# 140703_AriloTX_REV2_1_0.net
KiCad netlist of a schematic drawn in EAGLE
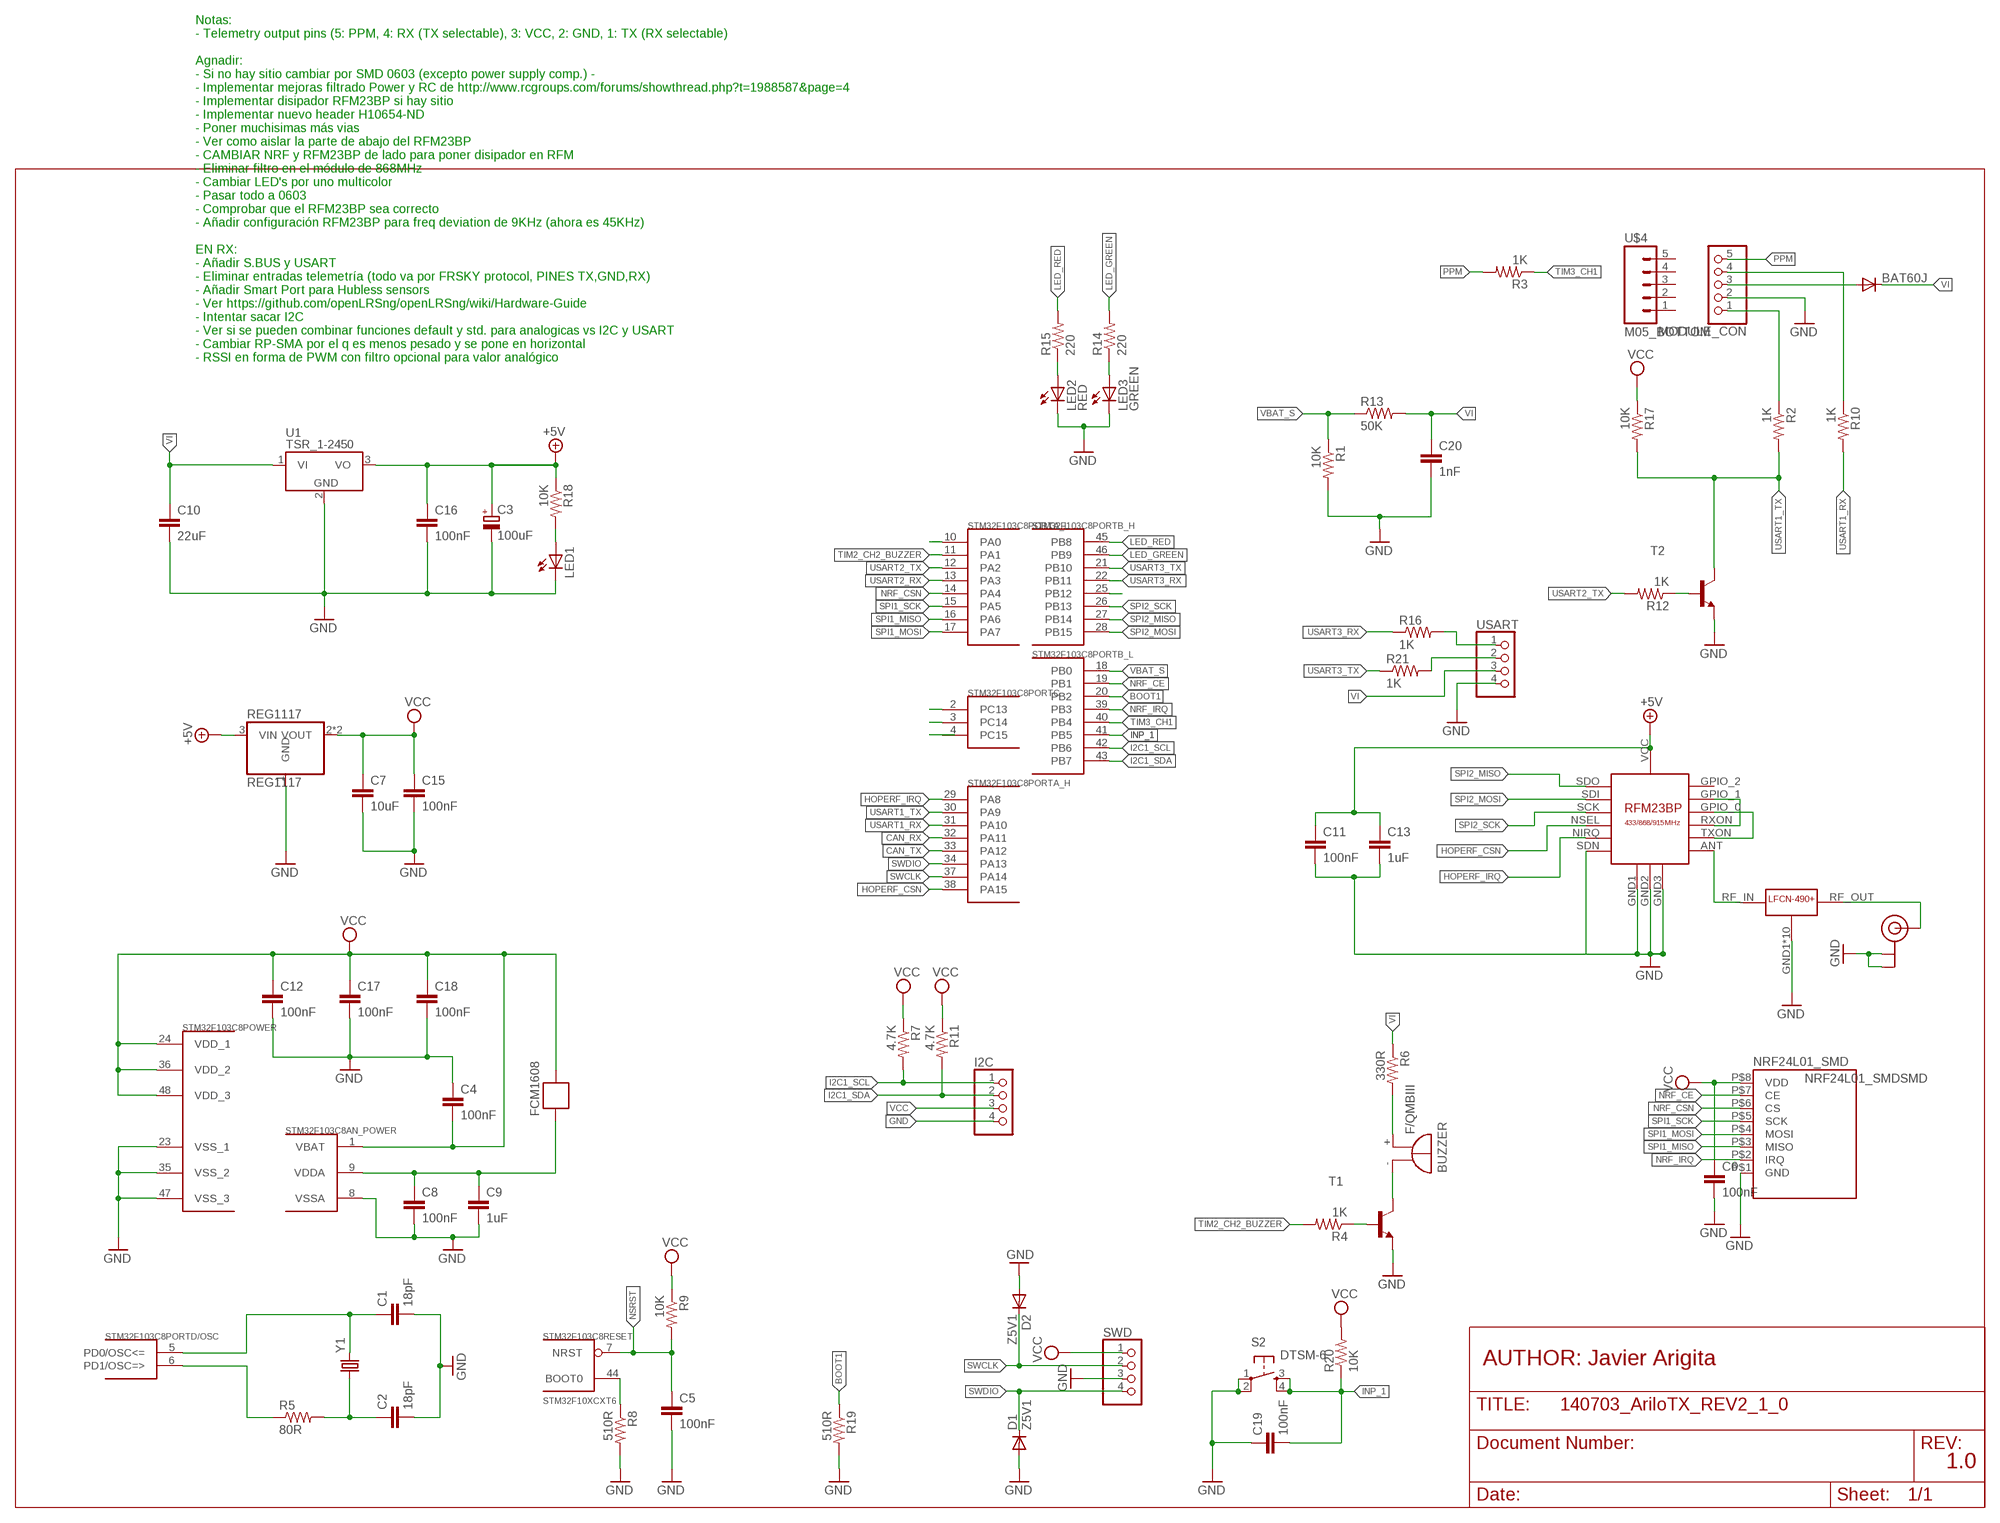
[diagram p0: schematic, sheet 1]

(export (version "E")
  (design (tool "Eeschema 10.0.6"))
  (components
    (comp (ref "BAT60J")
      (value "DIODE-SOD323-R")
      (footprint "eagle-import:SOD323-R")
      (libsource (lib "eagle-import") (part "DIODE-SOD323-R"))
    )
    (comp (ref "BUZZER")
      (value "F/QMBIII")
      (footprint "eagle-import:F_QMBIII")
      (libsource (lib "eagle-import") (part "F/QMBIII"))
    )
    (comp (ref "C1")
      (value "18pF")
      (footprint "eagle-import:C0805")
      (libsource (lib "eagle-import") (part "C-EUC0805"))
    )
    (comp (ref "C2")
      (value "18pF")
      (footprint "eagle-import:C0805")
      (libsource (lib "eagle-import") (part "C-EUC0805"))
    )
    (comp (ref "C3")
      (value "100uF")
      (footprint "eagle-import:SMC_B")
      (libsource (lib "eagle-import") (part "CPOL-EUSMCB"))
    )
    (comp (ref "C4")
      (value "100nF")
      (footprint "eagle-import:C0805")
      (libsource (lib "eagle-import") (part "C-EUC0805"))
    )
    (comp (ref "C5")
      (value "100nF")
      (footprint "eagle-import:C0805")
      (libsource (lib "eagle-import") (part "C-EUC0805"))
    )
    (comp (ref "C6")
      (value "100nF")
      (footprint "eagle-import:C0805")
      (libsource (lib "eagle-import") (part "C-EUC0805"))
    )
    (comp (ref "C7")
      (value "10uF")
      (footprint "eagle-import:C0805")
      (libsource (lib "eagle-import") (part "C-EUC0805"))
    )
    (comp (ref "C8")
      (value "100nF")
      (footprint "eagle-import:C0805")
      (libsource (lib "eagle-import") (part "C-EUC0805"))
    )
    (comp (ref "C9")
      (value "1uF")
      (footprint "eagle-import:C3216")
      (libsource (lib "eagle-import") (part "resistor_C-EUC3216"))
    )
    (comp (ref "C10")
      (value "22uF")
      (footprint "eagle-import:C3216")
      (libsource (lib "eagle-import") (part "resistor_C-EUC3216"))
    )
    (comp (ref "C11")
      (value "100nF")
      (footprint "eagle-import:C0805")
      (libsource (lib "eagle-import") (part "C-EUC0805"))
    )
    (comp (ref "C12")
      (value "100nF")
      (footprint "eagle-import:C0805")
      (libsource (lib "eagle-import") (part "C-EUC0805"))
    )
    (comp (ref "C13")
      (value "1uF")
      (footprint "eagle-import:C3216")
      (libsource (lib "eagle-import") (part "resistor_C-EUC3216"))
    )
    (comp (ref "C15")
      (value "100nF")
      (footprint "eagle-import:C0805")
      (libsource (lib "eagle-import") (part "C-EUC0805"))
    )
    (comp (ref "C16")
      (value "100nF")
      (footprint "eagle-import:C0805")
      (libsource (lib "eagle-import") (part "C-EUC0805"))
    )
    (comp (ref "C17")
      (value "100nF")
      (footprint "eagle-import:C0805")
      (libsource (lib "eagle-import") (part "C-EUC0805"))
    )
    (comp (ref "C18")
      (value "100nF")
      (footprint "eagle-import:C0805")
      (libsource (lib "eagle-import") (part "C-EUC0805"))
    )
    (comp (ref "C19")
      (value "100nF")
      (footprint "eagle-import:C0805")
      (libsource (lib "eagle-import") (part "C-EUC0805"))
    )
    (comp (ref "C20")
      (value "1nF")
      (footprint "eagle-import:C0805")
      (libsource (lib "eagle-import") (part "C-EUC0805"))
    )
    (comp (ref "D1")
      (value "Z5V1")
      (footprint "eagle-import:SOD323-R")
      (libsource (lib "eagle-import") (part "DIODE-SOD323-R"))
    )
    (comp (ref "D2")
      (value "Z5V1")
      (footprint "eagle-import:SOD323-R")
      (libsource (lib "eagle-import") (part "DIODE-SOD323-R"))
    )
    (comp (ref "FCM1608")
      (value "FERRITE-BEAD")
      (footprint "eagle-import:R0603")
      (libsource (lib "eagle-import") (part "FERRITE-BEAD"))
    )
    (comp (ref "I2C")
      (value "PINHD-1X4")
      (footprint "eagle-import:1X04")
      (libsource (lib "eagle-import") (part "PINHD-1X4"))
    )
    (comp (ref "LED1")
      (value "LED0805")
      (footprint "eagle-import:CHIPLED_0805")
      (libsource (lib "eagle-import") (part "LED0805"))
    )
    (comp (ref "LED2")
      (value "RED")
      (footprint "eagle-import:CHIP-LED0805")
      (libsource (lib "eagle-import") (part "LEDCHIP-LED0805"))
    )
    (comp (ref "LED3")
      (value "GREEN")
      (footprint "eagle-import:CHIP-LED0805")
      (libsource (lib "eagle-import") (part "LEDCHIP-LED0805"))
    )
    (comp (ref "MODULE_CON")
      (value "PINHD-1X5")
      (footprint "eagle-import:1X05")
      (libsource (lib "eagle-import") (part "PINHD-1X5"))
    )
    (comp (ref "NRF24L01_SMD")
      (value "NRF24L01_SMDSMD")
      (footprint "eagle-import:NRF24L01_SMD")
      (libsource (lib "eagle-import") (part "NRF24L01_SMDSMD"))
    )
    (comp (ref "R1")
      (value "10K")
      (footprint "eagle-import:R0805")
      (libsource (lib "eagle-import") (part "RESISTOR0805"))
    )
    (comp (ref "R2")
      (value "1K")
      (footprint "eagle-import:R0805")
      (libsource (lib "eagle-import") (part "RESISTOR0805"))
    )
    (comp (ref "R3")
      (value "1K")
      (footprint "eagle-import:R0805")
      (libsource (lib "eagle-import") (part "RESISTOR0805"))
    )
    (comp (ref "R4")
      (value "1K")
      (footprint "eagle-import:R0805")
      (libsource (lib "eagle-import") (part "RESISTOR0805"))
    )
    (comp (ref "R5")
      (value "80R")
      (footprint "eagle-import:R0805")
      (libsource (lib "eagle-import") (part "RESISTOR0805"))
    )
    (comp (ref "R6")
      (value "330R")
      (footprint "eagle-import:R0805")
      (libsource (lib "eagle-import") (part "RESISTOR0805"))
    )
    (comp (ref "R7")
      (value "4.7K")
      (footprint "eagle-import:R0805")
      (libsource (lib "eagle-import") (part "RESISTOR0805"))
    )
    (comp (ref "R8")
      (value "510R")
      (footprint "eagle-import:R0805")
      (libsource (lib "eagle-import") (part "RESISTOR0805"))
    )
    (comp (ref "R9")
      (value "10K")
      (footprint "eagle-import:R0805")
      (libsource (lib "eagle-import") (part "RESISTOR0805"))
    )
    (comp (ref "R10")
      (value "1K")
      (footprint "eagle-import:R0805")
      (libsource (lib "eagle-import") (part "RESISTOR0805"))
    )
    (comp (ref "R11")
      (value "4.7K")
      (footprint "eagle-import:R0805")
      (libsource (lib "eagle-import") (part "RESISTOR0805"))
    )
    (comp (ref "R12")
      (value "1K")
      (footprint "eagle-import:R0805")
      (libsource (lib "eagle-import") (part "RESISTOR0805"))
    )
    (comp (ref "R13")
      (value "50K")
      (footprint "eagle-import:R0805")
      (libsource (lib "eagle-import") (part "RESISTOR0805"))
    )
    (comp (ref "R14")
      (value "220")
      (footprint "eagle-import:R0805")
      (libsource (lib "eagle-import") (part "RESISTOR0805"))
    )
    (comp (ref "R15")
      (value "220")
      (footprint "eagle-import:R0805")
      (libsource (lib "eagle-import") (part "RESISTOR0805"))
    )
    (comp (ref "R16")
      (value "1K")
      (footprint "eagle-import:R0805")
      (libsource (lib "eagle-import") (part "RESISTOR0805"))
    )
    (comp (ref "R17")
      (value "10K")
      (footprint "eagle-import:R0805")
      (libsource (lib "eagle-import") (part "RESISTOR0805"))
    )
    (comp (ref "R18")
      (value "10K")
      (footprint "eagle-import:R0805")
      (libsource (lib "eagle-import") (part "RESISTOR0805"))
    )
    (comp (ref "R19")
      (value "510R")
      (footprint "eagle-import:R0805")
      (libsource (lib "eagle-import") (part "RESISTOR0805"))
    )
    (comp (ref "R20")
      (value "10K")
      (footprint "eagle-import:R0805")
      (libsource (lib "eagle-import") (part "RESISTOR0805"))
    )
    (comp (ref "R21")
      (value "1K")
      (footprint "eagle-import:R0805")
      (libsource (lib "eagle-import") (part "RESISTOR0805"))
    )
    (comp (ref "REG1117")
      (value "REG1117")
      (footprint "eagle-import:SOT223")
      (libsource (lib "eagle-import") (part "REG1117"))
    )
    (comp (ref "S2")
      (value "DTSM-6")
      (footprint "eagle-import:DTSM-6")
      (libsource (lib "eagle-import") (part "DTSM-6"))
    )
    (comp (ref "STM32F103C8")
      (value "STM32F10XCXT6")
      (footprint "eagle-import:TQFP48")
      (libsource (lib "eagle-import") (part "STM32F10XCXT6"))
    )
    (comp (ref "SWD")
      (value "PINHD-1X4")
      (footprint "eagle-import:1X04")
      (libsource (lib "eagle-import") (part "PINHD-1X4"))
    )
    (comp (ref "T1")
      (value "BC848-NPN-SOT23-BEC")
      (footprint "eagle-import:SOT23-BEC")
      (libsource (lib "eagle-import") (part "-NPN-SOT23-BECBC848"))
    )
    (comp (ref "T2")
      (value "BC848-NPN-SOT23-BEC")
      (footprint "eagle-import:SOT23-BEC")
      (libsource (lib "eagle-import") (part "-NPN-SOT23-BECBC848"))
    )
    (comp (ref "U$1")
      (value "RFM23BP")
      (footprint "eagle-import:RFM23BP")
      (libsource (lib "eagle-import") (part "RFM23BP"))
    )
    (comp (ref "U$2")
      (value "LFCN490+")
      (footprint "eagle-import:LFCN490+")
      (libsource (lib "eagle-import") (part "LFCN490+"))
    )
    (comp (ref "U$3")
      (value "U.FL")
      (footprint "eagle-import:U.FL")
      (libsource (lib "eagle-import") (part "U.FL"))
    )
    (comp (ref "U$4")
      (value "M05_BOTTOM")
      (footprint "eagle-import:M05_BOTTOM")
      (libsource (lib "eagle-import") (part "M05_BOTTOM"))
    )
    (comp (ref "U1")
      (value "TSR_1-2450")
      (footprint "eagle-import:TSR-1")
      (libsource (lib "eagle-import") (part "TSR_1-2450"))
    )
    (comp (ref "USART")
      (value "PINHD-1X4")
      (footprint "eagle-import:1X04")
      (libsource (lib "eagle-import") (part "PINHD-1X4"))
    )
    (comp (ref "Y1")
      (value "CRYSTAL5X3")
      (footprint "eagle-import:CRYSTAL-SMD-5X3")
      (libsource (lib "eagle-import") (part "CRYSTAL5X3"))
    )
  )
  (nets
    (net (code "1") (name "+5V") (class "Default")
      (node (ref "C11") (pin "1") (pinfunction "1_1") (pintype "passive"))
      (node (ref "C13") (pin "1") (pinfunction "1_1") (pintype "passive"))
      (node (ref "C16") (pin "1") (pinfunction "1_1") (pintype "passive"))
      (node (ref "C3") (pin "+") (pinfunction "+_+") (pintype "passive"))
      (node (ref "R18") (pin "1") (pinfunction "1_1") (pintype "passive"))
      (node (ref "REG1117") (pin "3") (pinfunction "VIN_3") (pintype "input"))
      (node (ref "U$1") (pin "VCC") (pinfunction "VCC_VCC") (pintype "power_in"))
      (node (ref "U1") (pin "3") (pinfunction "VO_3") (pintype "power_in"))
    )
    (net (code "2") (name "BOOT1") (class "Default")
      (node (ref "R19") (pin "1") (pinfunction "1_1") (pintype "passive"))
      (node (ref "STM32F103C8") (pin "20") (pinfunction "PB2_20") (pintype "bidirectional"))
    )
    (net (code "3") (name "CAN_RX") (class "Default")
      (node (ref "STM32F103C8") (pin "32") (pinfunction "PA11_32") (pintype "bidirectional"))
    )
    (net (code "4") (name "CAN_TX") (class "Default")
      (node (ref "STM32F103C8") (pin "33") (pinfunction "PA12_33") (pintype "bidirectional"))
    )
    (net (code "5") (name "GND") (class "Default")
      (node (ref "C1") (pin "2") (pinfunction "2_2") (pintype "passive"))
      (node (ref "C10") (pin "2") (pinfunction "2_2") (pintype "passive"))
      (node (ref "C11") (pin "2") (pinfunction "2_2") (pintype "passive"))
      (node (ref "C12") (pin "2") (pinfunction "2_2") (pintype "passive"))
      (node (ref "C13") (pin "2") (pinfunction "2_2") (pintype "passive"))
      (node (ref "C15") (pin "2") (pinfunction "2_2") (pintype "passive"))
      (node (ref "C16") (pin "2") (pinfunction "2_2") (pintype "passive"))
      (node (ref "C17") (pin "2") (pinfunction "2_2") (pintype "passive"))
      (node (ref "C18") (pin "2") (pinfunction "2_2") (pintype "passive"))
      (node (ref "C19") (pin "1") (pinfunction "1_1") (pintype "passive"))
      (node (ref "C2") (pin "2") (pinfunction "2_2") (pintype "passive"))
      (node (ref "C20") (pin "2") (pinfunction "2_2") (pintype "passive"))
      (node (ref "C3") (pin "-") (pinfunction "-_-") (pintype "passive"))
      (node (ref "C4") (pin "1") (pinfunction "1_1") (pintype "passive"))
      (node (ref "C5") (pin "2") (pinfunction "2_2") (pintype "passive"))
      (node (ref "C6") (pin "2") (pinfunction "2_2") (pintype "passive"))
      (node (ref "C7") (pin "2") (pinfunction "2_2") (pintype "passive"))
      (node (ref "C8") (pin "2") (pinfunction "2_2") (pintype "passive"))
      (node (ref "C9") (pin "2") (pinfunction "2_2") (pintype "passive"))
      (node (ref "D1") (pin "A") (pinfunction "A_A") (pintype "passive"))
      (node (ref "D2") (pin "A") (pinfunction "A_A") (pintype "passive"))
      (node (ref "I2C") (pin "4") (pinfunction "4_4") (pintype "passive"))
      (node (ref "LED1") (pin "C") (pinfunction "C_C") (pintype "passive"))
      (node (ref "LED2") (pin "C") (pinfunction "C_C") (pintype "passive"))
      (node (ref "LED3") (pin "C") (pinfunction "C_C") (pintype "passive"))
      (node (ref "MODULE_CON") (pin "2") (pinfunction "2_2") (pintype "passive"))
      (node (ref "NRF24L01_SMD") (pin "P$1") (pinfunction "GND_P$1") (pintype "power_in"))
      (node (ref "R1") (pin "2") (pinfunction "2_2") (pintype "passive"))
      (node (ref "R19") (pin "2") (pinfunction "2_2") (pintype "passive"))
      (node (ref "R8") (pin "2") (pinfunction "2_2") (pintype "passive"))
      (node (ref "REG1117") (pin "1") (pinfunction "GND_1") (pintype "power_in"))
      (node (ref "S2") (pin "1") (pinfunction "1_1") (pintype "passive"))
      (node (ref "S2") (pin "2") (pinfunction "2_2") (pintype "passive"))
      (node (ref "STM32F103C8") (pin "23") (pinfunction "VSS_1_23") (pintype "power_in"))
      (node (ref "STM32F103C8") (pin "35") (pinfunction "VSS_2_35") (pintype "power_in"))
      (node (ref "STM32F103C8") (pin "47") (pinfunction "VSS_3_47") (pintype "power_in"))
      (node (ref "STM32F103C8") (pin "8") (pinfunction "VSSA_8") (pintype "power_in"))
      (node (ref "SWD") (pin "3") (pinfunction "3_3") (pintype "passive"))
      (node (ref "T1") (pin "E") (pinfunction "E_E") (pintype "passive"))
      (node (ref "T2") (pin "E") (pinfunction "E_E") (pintype "passive"))
      (node (ref "U$1") (pin "GND1") (pinfunction "GND1_GND1") (pintype "power_in"))
      (node (ref "U$1") (pin "GND2") (pinfunction "GND2_GND2") (pintype "power_in"))
      (node (ref "U$1") (pin "GND3") (pinfunction "GND3_GND3") (pintype "power_in"))
      (node (ref "U$1") (pin "SDN") (pinfunction "SDN_SDN") (pintype "bidirectional"))
      (node (ref "U$2") (pin "GND1") (pinfunction "GND_GND1") (pintype "bidirectional"))
      (node (ref "U$2") (pin "GND10") (pinfunction "GND_GND10") (pintype "bidirectional"))
      (node (ref "U$2") (pin "GND2") (pinfunction "GND_GND2") (pintype "bidirectional"))
      (node (ref "U$2") (pin "GND3") (pinfunction "GND_GND3") (pintype "bidirectional"))
      (node (ref "U$2") (pin "GND4") (pinfunction "GND_GND4") (pintype "bidirectional"))
      (node (ref "U$2") (pin "GND5") (pinfunction "GND_GND5") (pintype "bidirectional"))
      (node (ref "U$2") (pin "GND6") (pinfunction "GND_GND6") (pintype "bidirectional"))
      (node (ref "U$2") (pin "GND7") (pinfunction "GND_GND7") (pintype "bidirectional"))
      (node (ref "U$2") (pin "GND8") (pinfunction "GND_GND8") (pintype "bidirectional"))
      (node (ref "U$2") (pin "GND9") (pinfunction "GND_GND9") (pintype "bidirectional"))
      (node (ref "U$3") (pin "P$1") (pinfunction "GND_P$1") (pintype "bidirectional"))
      (node (ref "U$3") (pin "P$2") (pinfunction "GND_P$2") (pintype "bidirectional"))
      (node (ref "U1") (pin "2") (pinfunction "GND_2") (pintype "power_in"))
      (node (ref "USART") (pin "4") (pinfunction "4_4") (pintype "passive"))
    )
    (net (code "6") (name "HOPERF_CSN") (class "Default")
      (node (ref "STM32F103C8") (pin "38") (pinfunction "PA15_38") (pintype "bidirectional"))
      (node (ref "U$1") (pin "NSEL") (pinfunction "NSEL_NSEL") (pintype "bidirectional"))
    )
    (net (code "7") (name "HOPERF_IRQ") (class "Default")
      (node (ref "STM32F103C8") (pin "29") (pinfunction "PA8_29") (pintype "bidirectional"))
      (node (ref "U$1") (pin "NIRQ") (pinfunction "NIRQ_NIRQ") (pintype "bidirectional"))
    )
    (net (code "8") (name "I2C1_SCL") (class "Default")
      (node (ref "I2C") (pin "1") (pinfunction "1_1") (pintype "passive"))
      (node (ref "R7") (pin "2") (pinfunction "2_2") (pintype "passive"))
      (node (ref "STM32F103C8") (pin "42") (pinfunction "PB6_42") (pintype "bidirectional"))
    )
    (net (code "9") (name "I2C1_SDA") (class "Default")
      (node (ref "I2C") (pin "2") (pinfunction "2_2") (pintype "passive"))
      (node (ref "R11") (pin "2") (pinfunction "2_2") (pintype "passive"))
      (node (ref "STM32F103C8") (pin "43") (pinfunction "PB7_43") (pintype "bidirectional"))
    )
    (net (code "10") (name "INP_1") (class "Default")
      (node (ref "C19") (pin "2") (pinfunction "2_2") (pintype "passive"))
      (node (ref "R20") (pin "1") (pinfunction "1_1") (pintype "passive"))
      (node (ref "S2") (pin "3") (pinfunction "3_3") (pintype "passive"))
      (node (ref "S2") (pin "4") (pinfunction "4_4") (pintype "passive"))
      (node (ref "STM32F103C8") (pin "41") (pinfunction "PB5_41") (pintype "bidirectional"))
    )
    (net (code "11") (name "LED_GREEN") (class "Default")
      (node (ref "R14") (pin "2") (pinfunction "2_2") (pintype "passive"))
      (node (ref "STM32F103C8") (pin "46") (pinfunction "PB9_46") (pintype "bidirectional"))
    )
    (net (code "12") (name "LED_RED") (class "Default")
      (node (ref "R15") (pin "2") (pinfunction "2_2") (pintype "passive"))
      (node (ref "STM32F103C8") (pin "45") (pinfunction "PB8_45") (pintype "bidirectional"))
    )
    (net (code "13") (name "NRF_CE") (class "Default")
      (node (ref "NRF24L01_SMD") (pin "P$7") (pinfunction "CE_P$7") (pintype "input"))
      (node (ref "STM32F103C8") (pin "19") (pinfunction "PB1_19") (pintype "bidirectional"))
    )
    (net (code "14") (name "NRF_CSN") (class "Default")
      (node (ref "NRF24L01_SMD") (pin "P$6") (pinfunction "CS_P$6") (pintype "input"))
      (node (ref "STM32F103C8") (pin "14") (pinfunction "PA4_14") (pintype "bidirectional"))
    )
    (net (code "15") (name "NRF_IRQ") (class "Default")
      (node (ref "NRF24L01_SMD") (pin "P$2") (pinfunction "IRQ_P$2") (pintype "output"))
      (node (ref "STM32F103C8") (pin "39") (pinfunction "PB3_39") (pintype "bidirectional"))
    )
    (net (code "16") (name "NSRST") (class "Default")
      (node (ref "C5") (pin "1") (pinfunction "1_1") (pintype "passive"))
      (node (ref "R9") (pin "2") (pinfunction "2_2") (pintype "passive"))
      (node (ref "STM32F103C8") (pin "7") (pinfunction "NRST_7") (pintype "input"))
    )
    (net (code "17") (name "Net-(BAT60J-PadA)") (class "Default")
      (node (ref "BAT60J") (pin "A") (pinfunction "A_A") (pintype "passive"))
      (node (ref "MODULE_CON") (pin "3") (pinfunction "3_3") (pintype "passive"))
    )
    (net (code "18") (name "Net-(BUZZER-+)") (class "Default")
      (node (ref "BUZZER") (pin "-") (pinfunction "+_-") (pintype "passive"))
      (node (ref "T1") (pin "C") (pinfunction "C_C") (pintype "passive"))
    )
    (net (code "19") (name "Net-(BUZZER--)") (class "Default")
      (node (ref "BUZZER") (pin "+") (pinfunction "-_+") (pintype "passive"))
      (node (ref "R6") (pin "2") (pinfunction "2_2") (pintype "passive"))
    )
    (net (code "20") (name "Net-(C2-Pad1)") (class "Default")
      (node (ref "C2") (pin "1") (pinfunction "1_1") (pintype "passive"))
      (node (ref "R5") (pin "2") (pinfunction "2_2") (pintype "passive"))
      (node (ref "Y1") (pin "1") (pinfunction "1_1") (pintype "passive"))
    )
    (net (code "21") (name "Net-(FCM1608-P$2)") (class "Default")
      (node (ref "C8") (pin "1") (pinfunction "1_1") (pintype "passive"))
      (node (ref "C9") (pin "1") (pinfunction "1_1") (pintype "passive"))
      (node (ref "FCM1608") (pin "2") (pinfunction "P$2_2") (pintype "bidirectional"))
      (node (ref "STM32F103C8") (pin "9") (pinfunction "VDDA_9") (pintype "power_in"))
    )
    (net (code "22") (name "Net-(LED1-PadA)") (class "Default")
      (node (ref "LED1") (pin "A") (pinfunction "A_A") (pintype "passive"))
      (node (ref "R18") (pin "2") (pinfunction "2_2") (pintype "passive"))
    )
    (net (code "23") (name "Net-(LED2-PadA)") (class "Default")
      (node (ref "LED2") (pin "A") (pinfunction "A_A") (pintype "passive"))
      (node (ref "R15") (pin "1") (pinfunction "1_1") (pintype "passive"))
    )
    (net (code "24") (name "Net-(LED3-PadA)") (class "Default")
      (node (ref "LED3") (pin "A") (pinfunction "A_A") (pintype "passive"))
      (node (ref "R14") (pin "1") (pinfunction "1_1") (pintype "passive"))
    )
    (net (code "25") (name "Net-(MODULE_CON-Pad1)") (class "Default")
      (node (ref "MODULE_CON") (pin "1") (pinfunction "1_1") (pintype "passive"))
      (node (ref "R2") (pin "1") (pinfunction "1_1") (pintype "passive"))
    )
    (net (code "26") (name "Net-(MODULE_CON-Pad4)") (class "Default")
      (node (ref "MODULE_CON") (pin "4") (pinfunction "4_4") (pintype "passive"))
      (node (ref "R10") (pin "1") (pinfunction "1_1") (pintype "passive"))
    )
    (net (code "27") (name "Net-(R4-Pad1)") (class "Default")
      (node (ref "R4") (pin "1") (pinfunction "1_1") (pintype "passive"))
      (node (ref "T1") (pin "B") (pinfunction "B_B") (pintype "passive"))
    )
    (net (code "28") (name "Net-(R12-Pad1)") (class "Default")
      (node (ref "R12") (pin "1") (pinfunction "1_1") (pintype "passive"))
      (node (ref "T2") (pin "B") (pinfunction "B_B") (pintype "passive"))
    )
    (net (code "29") (name "Net-(R16-Pad2)") (class "Default")
      (node (ref "R16") (pin "2") (pinfunction "2_2") (pintype "passive"))
      (node (ref "USART") (pin "1") (pinfunction "1_1") (pintype "passive"))
    )
    (net (code "30") (name "Net-(R21-Pad2)") (class "Default")
      (node (ref "R21") (pin "2") (pinfunction "2_2") (pintype "passive"))
      (node (ref "USART") (pin "2") (pinfunction "2_2") (pintype "passive"))
    )
    (net (code "31") (name "Net-(STM32F103C8G-PD0{slash}OSC<=)") (class "Default")
      (node (ref "C1") (pin "1") (pinfunction "1_1") (pintype "passive"))
      (node (ref "STM32F103C8") (pin "5") (pinfunction "PD0/OSC<=_5") (pintype "bidirectional"))
      (node (ref "Y1") (pin "3") (pinfunction "2_3") (pintype "passive"))
    )
    (net (code "32") (name "Net-(STM32F103C8G-PD1{slash}OSC=>)") (class "Default")
      (node (ref "R5") (pin "1") (pinfunction "1_1") (pintype "passive"))
      (node (ref "STM32F103C8") (pin "6") (pinfunction "PD1/OSC=>_6") (pintype "bidirectional"))
    )
    (net (code "33") (name "Net-(STM32F103C8I-BOOT0)") (class "Default")
      (node (ref "R8") (pin "1") (pinfunction "1_1") (pintype "passive"))
      (node (ref "STM32F103C8") (pin "44") (pinfunction "BOOT0_44") (pintype "input"))
    )
    (net (code "34") (name "Net-(U$1-PadGPIO_0)") (class "Default")
      (node (ref "U$1") (pin "GPIO_0") (pinfunction "GPIO_0_GPIO_0") (pintype "bidirectional"))
      (node (ref "U$1") (pin "TXON") (pinfunction "TXON_TXON") (pintype "bidirectional"))
    )
    (net (code "35") (name "Net-(U$1-PadGPIO_1)") (class "Default")
      (node (ref "U$1") (pin "GPIO_1") (pinfunction "GPIO_1_GPIO_1") (pintype "bidirectional"))
      (node (ref "U$1") (pin "RXON") (pinfunction "RXON_RXON") (pintype "bidirectional"))
    )
    (net (code "36") (name "Net-(U$2-RF_INP)") (class "Default")
      (node (ref "U$1") (pin "ANT") (pinfunction "ANT_ANT") (pintype "bidirectional"))
      (node (ref "U$2") (pin "RF_IN") (pinfunction "RF_INP_RF_IN") (pintype "bidirectional"))
    )
    (net (code "37") (name "Net-(U$2-RF_OUTP)") (class "Default")
      (node (ref "U$2") (pin "RF_OUT") (pinfunction "RF_OUTP_RF_OUT") (pintype "bidirectional"))
      (node (ref "U$3") (pin "P$3") (pinfunction "SIGNAL_P$3") (pintype "bidirectional"))
    )
    (net (code "38") (name "PPM") (class "Default")
      (node (ref "MODULE_CON") (pin "5") (pinfunction "5_5") (pintype "passive"))
      (node (ref "R3") (pin "2") (pinfunction "2_2") (pintype "passive"))
    )
    (net (code "39") (name "SPI1_MISO") (class "Default")
      (node (ref "NRF24L01_SMD") (pin "P$3") (pinfunction "MISO_P$3") (pintype "output"))
      (node (ref "STM32F103C8") (pin "16") (pinfunction "PA6_16") (pintype "bidirectional"))
    )
    (net (code "40") (name "SPI1_MOSI") (class "Default")
      (node (ref "NRF24L01_SMD") (pin "P$4") (pinfunction "MOSI_P$4") (pintype "input"))
      (node (ref "STM32F103C8") (pin "17") (pinfunction "PA7_17") (pintype "bidirectional"))
    )
    (net (code "41") (name "SPI1_SCK") (class "Default")
      (node (ref "NRF24L01_SMD") (pin "P$5") (pinfunction "SCK_P$5") (pintype "input"))
      (node (ref "STM32F103C8") (pin "15") (pinfunction "PA5_15") (pintype "bidirectional"))
    )
    (net (code "42") (name "SPI2_MISO") (class "Default")
      (node (ref "STM32F103C8") (pin "27") (pinfunction "PB14_27") (pintype "bidirectional"))
      (node (ref "U$1") (pin "SDO") (pinfunction "SDO_SDO") (pintype "bidirectional"))
    )
    (net (code "43") (name "SPI2_MOSI") (class "Default")
      (node (ref "STM32F103C8") (pin "28") (pinfunction "PB15_28") (pintype "bidirectional"))
      (node (ref "U$1") (pin "SDI") (pinfunction "SDI_SDI") (pintype "bidirectional"))
    )
    (net (code "44") (name "SPI2_SCK") (class "Default")
      (node (ref "STM32F103C8") (pin "26") (pinfunction "PB13_26") (pintype "bidirectional"))
      (node (ref "U$1") (pin "SCK") (pinfunction "SCK_SCK") (pintype "bidirectional"))
    )
    (net (code "45") (name "SWCLK") (class "Default")
      (node (ref "D2") (pin "C") (pinfunction "C_C") (pintype "passive"))
      (node (ref "STM32F103C8") (pin "37") (pinfunction "PA14_37") (pintype "bidirectional"))
      (node (ref "SWD") (pin "2") (pinfunction "2_2") (pintype "passive"))
    )
    (net (code "46") (name "SWDIO") (class "Default")
      (node (ref "D1") (pin "C") (pinfunction "C_C") (pintype "passive"))
      (node (ref "STM32F103C8") (pin "34") (pinfunction "PA13_34") (pintype "bidirectional"))
      (node (ref "SWD") (pin "4") (pinfunction "4_4") (pintype "passive"))
    )
    (net (code "47") (name "TIM2_CH2_BUZZER") (class "Default")
      (node (ref "R4") (pin "2") (pinfunction "2_2") (pintype "passive"))
      (node (ref "STM32F103C8") (pin "11") (pinfunction "PA1_11") (pintype "bidirectional"))
    )
    (net (code "48") (name "TIM3_CH1") (class "Default")
      (node (ref "R3") (pin "1") (pinfunction "1_1") (pintype "passive"))
      (node (ref "STM32F103C8") (pin "40") (pinfunction "PB4_40") (pintype "bidirectional"))
    )
    (net (code "49") (name "USART1_RX") (class "Default")
      (node (ref "R10") (pin "2") (pinfunction "2_2") (pintype "passive"))
      (node (ref "STM32F103C8") (pin "31") (pinfunction "PA10_31") (pintype "bidirectional"))
    )
    (net (code "50") (name "USART1_TX") (class "Default")
      (node (ref "R17") (pin "2") (pinfunction "2_2") (pintype "passive"))
      (node (ref "R2") (pin "2") (pinfunction "2_2") (pintype "passive"))
      (node (ref "STM32F103C8") (pin "30") (pinfunction "PA9_30") (pintype "bidirectional"))
      (node (ref "T2") (pin "C") (pinfunction "C_C") (pintype "passive"))
    )
    (net (code "51") (name "USART2_RX") (class "Default")
      (node (ref "STM32F103C8") (pin "13") (pinfunction "PA3_13") (pintype "bidirectional"))
    )
    (net (code "52") (name "USART2_TX") (class "Default")
      (node (ref "R12") (pin "2") (pinfunction "2_2") (pintype "passive"))
      (node (ref "STM32F103C8") (pin "12") (pinfunction "PA2_12") (pintype "bidirectional"))
    )
    (net (code "53") (name "USART3_RX") (class "Default")
      (node (ref "R16") (pin "1") (pinfunction "1_1") (pintype "passive"))
      (node (ref "STM32F103C8") (pin "22") (pinfunction "PB11_22") (pintype "bidirectional"))
    )
    (net (code "54") (name "USART3_TX") (class "Default")
      (node (ref "R21") (pin "1") (pinfunction "1_1") (pintype "passive"))
      (node (ref "STM32F103C8") (pin "21") (pinfunction "PB10_21") (pintype "bidirectional"))
    )
    (net (code "55") (name "VBAT_S") (class "Default")
      (node (ref "R1") (pin "1") (pinfunction "1_1") (pintype "passive"))
      (node (ref "R13") (pin "1") (pinfunction "1_1") (pintype "passive"))
      (node (ref "STM32F103C8") (pin "18") (pinfunction "PB0_18") (pintype "bidirectional"))
    )
    (net (code "56") (name "VCC") (class "Default")
      (node (ref "C12") (pin "1") (pinfunction "1_1") (pintype "passive"))
      (node (ref "C15") (pin "1") (pinfunction "1_1") (pintype "passive"))
      (node (ref "C17") (pin "1") (pinfunction "1_1") (pintype "passive"))
      (node (ref "C18") (pin "1") (pinfunction "1_1") (pintype "passive"))
      (node (ref "C4") (pin "2") (pinfunction "2_2") (pintype "passive"))
      (node (ref "C6") (pin "1") (pinfunction "1_1") (pintype "passive"))
      (node (ref "C7") (pin "1") (pinfunction "1_1") (pintype "passive"))
      (node (ref "FCM1608") (pin "1") (pinfunction "P$1_1") (pintype "bidirectional"))
      (node (ref "I2C") (pin "3") (pinfunction "3_3") (pintype "passive"))
      (node (ref "NRF24L01_SMD") (pin "P$8") (pinfunction "VDD_P$8") (pintype "bidirectional"))
      (node (ref "R11") (pin "1") (pinfunction "1_1") (pintype "passive"))
      (node (ref "R17") (pin "1") (pinfunction "1_1") (pintype "passive"))
      (node (ref "R20") (pin "2") (pinfunction "2_2") (pintype "passive"))
      (node (ref "R7") (pin "1") (pinfunction "1_1") (pintype "passive"))
      (node (ref "R9") (pin "1") (pinfunction "1_1") (pintype "passive"))
      (node (ref "REG1117") (pin "2") (pinfunction "VOUT_2") (pintype "power_in"))
      (node (ref "REG1117") (pin "4") (pinfunction "VOUT_4") (pintype "power_in"))
      (node (ref "STM32F103C8") (pin "1") (pinfunction "VBAT_1") (pintype "power_in"))
      (node (ref "STM32F103C8") (pin "24") (pinfunction "VDD_1_24") (pintype "power_in"))
      (node (ref "STM32F103C8") (pin "36") (pinfunction "VDD_2_36") (pintype "power_in"))
      (node (ref "STM32F103C8") (pin "48") (pinfunction "VDD_3_48") (pintype "power_in"))
      (node (ref "SWD") (pin "1") (pinfunction "1_1") (pintype "passive"))
    )
    (net (code "57") (name "VI") (class "Default")
      (node (ref "BAT60J") (pin "C") (pinfunction "C_C") (pintype "passive"))
      (node (ref "C10") (pin "1") (pinfunction "1_1") (pintype "passive"))
      (node (ref "C20") (pin "1") (pinfunction "1_1") (pintype "passive"))
      (node (ref "R13") (pin "2") (pinfunction "2_2") (pintype "passive"))
      (node (ref "R6") (pin "1") (pinfunction "1_1") (pintype "passive"))
      (node (ref "U1") (pin "1") (pinfunction "VI_1") (pintype "power_in"))
      (node (ref "USART") (pin "3") (pinfunction "3_3") (pintype "passive"))
    )
    (net (code "58") (name "unconnected-(STM32F103C8C-PA0-Pad10)") (class "Default")
      (node (ref "STM32F103C8") (pin "10") (pinfunction "PA0_10") (pintype "bidirectional"))
    )
    (net (code "59") (name "unconnected-(STM32F103C8D-PB12-Pad25)") (class "Default")
      (node (ref "STM32F103C8") (pin "25") (pinfunction "PB12_25") (pintype "bidirectional"))
    )
    (net (code "60") (name "unconnected-(STM32F103C8F-PC13-Pad2)") (class "Default")
      (node (ref "STM32F103C8") (pin "2") (pinfunction "PC13_2") (pintype "bidirectional"))
    )
    (net (code "61") (name "unconnected-(STM32F103C8F-PC14-Pad3)") (class "Default")
      (node (ref "STM32F103C8") (pin "3") (pinfunction "PC14_3") (pintype "bidirectional"))
    )
    (net (code "62") (name "unconnected-(STM32F103C8F-PC15-Pad4)") (class "Default")
      (node (ref "STM32F103C8") (pin "4") (pinfunction "PC15_4") (pintype "bidirectional"))
    )
    (net (code "63") (name "unconnected-(U$1-PadGPIO_2)") (class "Default")
      (node (ref "U$1") (pin "GPIO_2") (pinfunction "GPIO_2_GPIO_2") (pintype "bidirectional"))
    )
    (net (code "64") (name "unconnected-(U$4-Pad1)") (class "Default")
      (node (ref "U$4") (pin "1") (pinfunction "1_1") (pintype "passive"))
    )
    (net (code "65") (name "unconnected-(U$4-Pad2)") (class "Default")
      (node (ref "U$4") (pin "2") (pinfunction "2_2") (pintype "passive"))
    )
    (net (code "66") (name "unconnected-(U$4-Pad3)") (class "Default")
      (node (ref "U$4") (pin "3") (pinfunction "3_3") (pintype "passive"))
    )
    (net (code "67") (name "unconnected-(U$4-Pad4)") (class "Default")
      (node (ref "U$4") (pin "4") (pinfunction "4_4") (pintype "passive"))
    )
    (net (code "68") (name "unconnected-(U$4-Pad5)") (class "Default")
      (node (ref "U$4") (pin "5") (pinfunction "5_5") (pintype "passive"))
    )
  )
)
